# gps.net
KiCad netlist of a schematic drawn in EAGLE
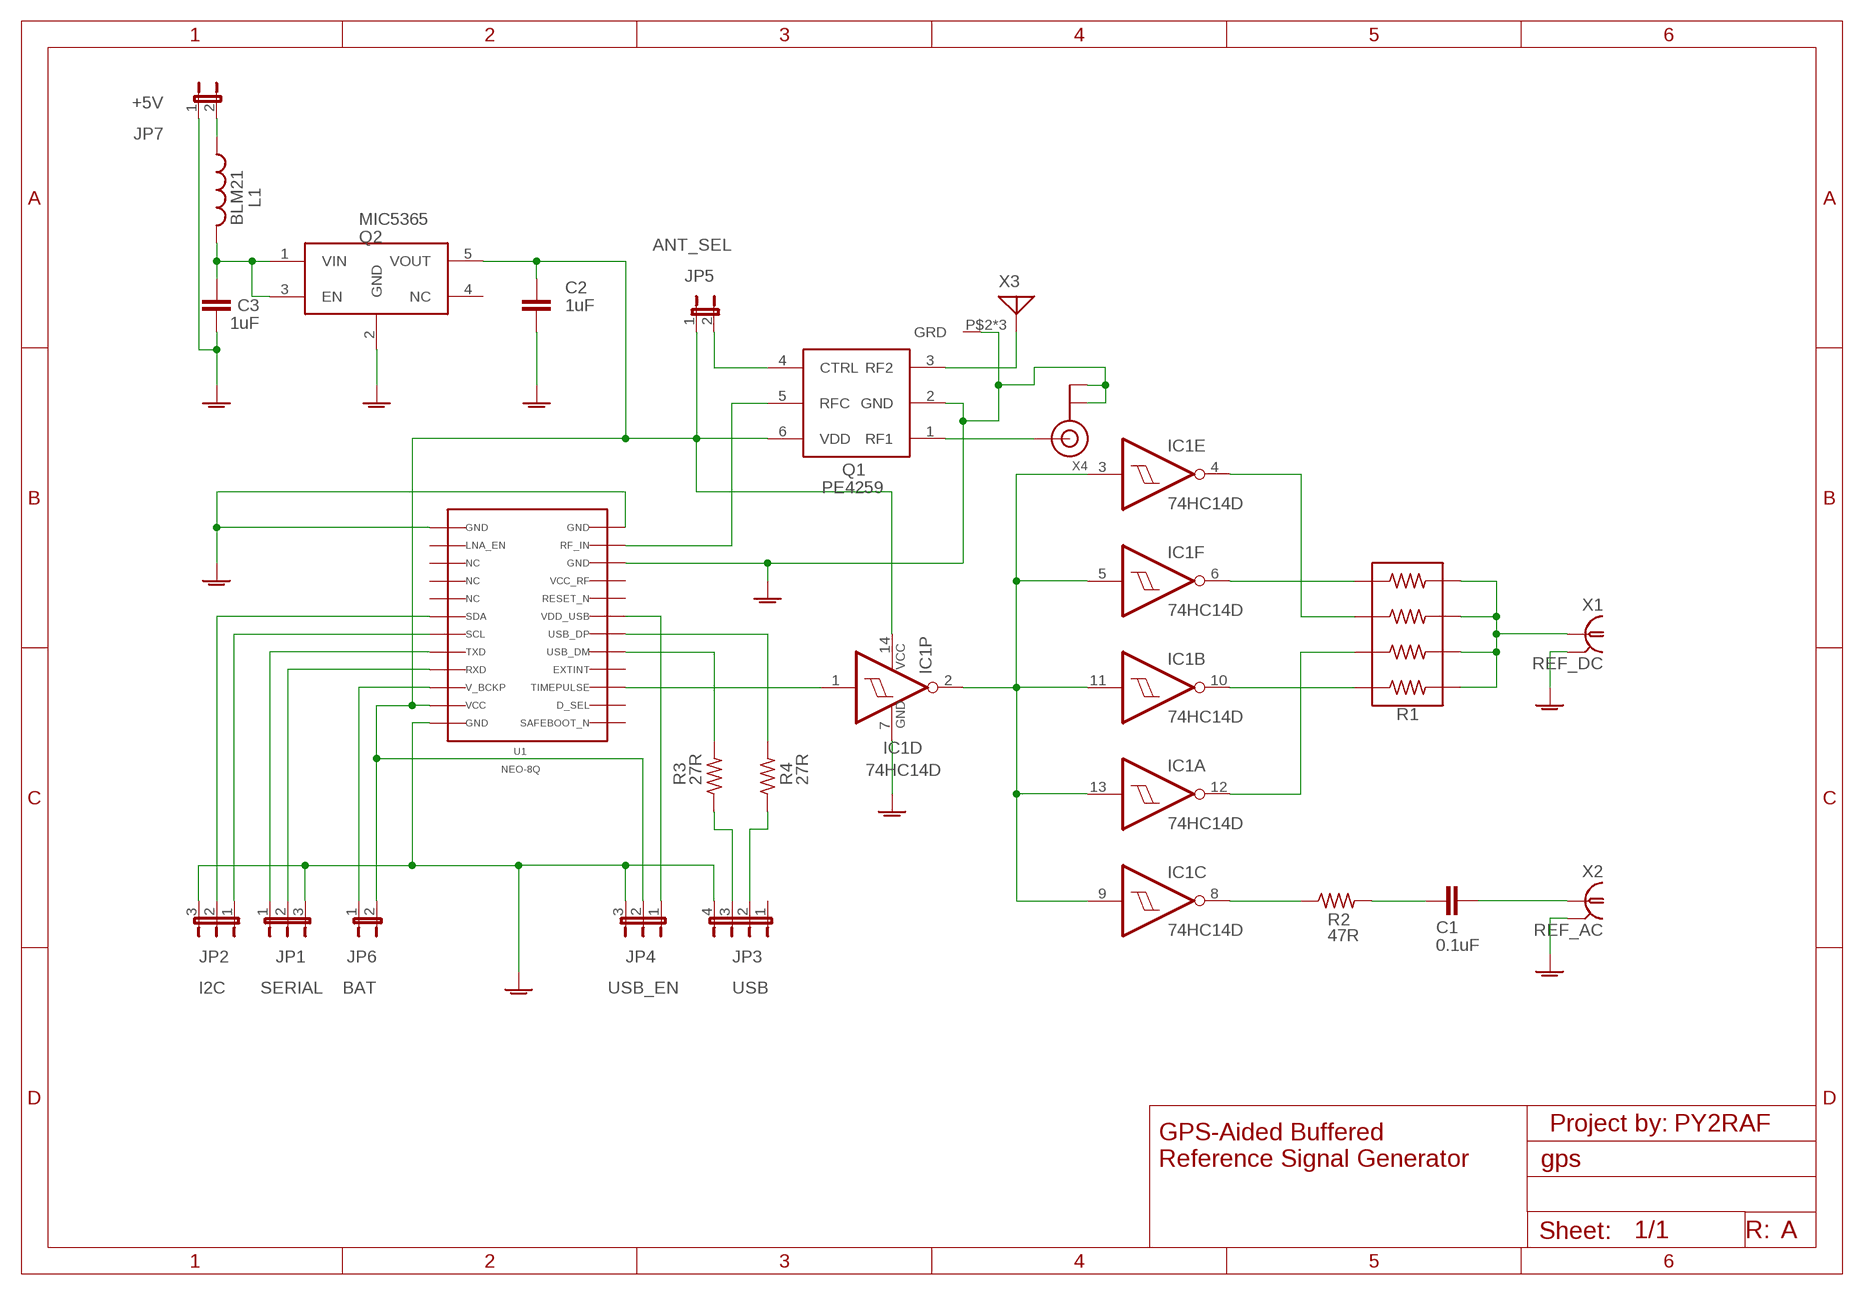
[diagram p0: schematic, sheet 1]

(export (version "E")
  (design (tool "Eeschema 10.0.6"))
  (components
    (comp (ref "C1")
      (value "0.1uF")
      (footprint "eagle-import:C1206")
      (libsource (lib "eagle-import") (part "C-EUC1206"))
    )
    (comp (ref "C2")
      (value "1uF")
      (footprint "eagle-import:C1206")
      (libsource (lib "eagle-import") (part "C-EUC1206"))
    )
    (comp (ref "C3")
      (value "1uF")
      (footprint "eagle-import:C1206")
      (libsource (lib "eagle-import") (part "C-EUC1206"))
    )
    (comp (ref "IC1")
      (value "74HC14D")
      (footprint "eagle-import:SO14")
      (libsource (lib "eagle-import") (part "7414DHC"))
    )
    (comp (ref "JP1")
      (value "SERIAL")
      (footprint "eagle-import:JP2")
      (libsource (lib "eagle-import") (part "JP2E"))
    )
    (comp (ref "JP2")
      (value "I2C")
      (footprint "eagle-import:JP2")
      (libsource (lib "eagle-import") (part "JP2E"))
    )
    (comp (ref "JP3")
      (value "USB")
      (footprint "eagle-import:JP4")
      (libsource (lib "eagle-import") (part "JP4E"))
    )
    (comp (ref "JP4")
      (value "USB_EN")
      (footprint "eagle-import:JP2")
      (libsource (lib "eagle-import") (part "JP2E"))
    )
    (comp (ref "JP5")
      (value "ANT_SEL")
      (footprint "eagle-import:JP1")
      (libsource (lib "eagle-import") (part "JP1E"))
    )
    (comp (ref "JP6")
      (value "BAT")
      (footprint "eagle-import:JP1")
      (libsource (lib "eagle-import") (part "JP1E"))
    )
    (comp (ref "JP7")
      (value "+5V")
      (footprint "eagle-import:JP1")
      (libsource (lib "eagle-import") (part "JP1E"))
    )
    (comp (ref "L1")
      (value "BLM21")
      (footprint "eagle-import:L2012C")
      (libsource (lib "eagle-import") (part "L-USL2012C"))
    )
    (comp (ref "Q1")
      (value "PE4259")
      (footprint "eagle-import:SC-70")
      (libsource (lib "eagle-import") (part "PE4259"))
    )
    (comp (ref "Q2")
      (value "MIC5365")
      (footprint "eagle-import:SOT23-5L")
      (libsource (lib "eagle-import") (part "MIC5365"))
    )
    (comp (ref "R1")
      (value "744C083")
      (footprint "eagle-import:1206X4")
      (libsource (lib "eagle-import") (part "744C083"))
    )
    (comp (ref "R2")
      (value "47R")
      (footprint "eagle-import:M1206")
      (libsource (lib "eagle-import") (part "R-US_M1206"))
    )
    (comp (ref "R3")
      (value "27R")
      (footprint "eagle-import:M1206")
      (libsource (lib "eagle-import") (part "R-US_M1206"))
    )
    (comp (ref "R4")
      (value "27R")
      (footprint "eagle-import:M1206")
      (libsource (lib "eagle-import") (part "R-US_M1206"))
    )
    (comp (ref "U1")
      (value "NEO-8Q")
      (footprint "eagle-import:NEO-7")
      (libsource (lib "eagle-import") (part "NEO-8"))
    )
    (comp (ref "X1")
      (value "REF_DC")
      (footprint "eagle-import:SMA-RF")
      (libsource (lib "eagle-import") (part "SMA-PCB"))
    )
    (comp (ref "X2")
      (value "REF_AC")
      (footprint "eagle-import:SMA-RF")
      (libsource (lib "eagle-import") (part "SMA-PCB"))
    )
    (comp (ref "X3")
      (value "ANT-GNSS-MLX")
      (footprint "eagle-import:MOLEX-GNSS")
      (libsource (lib "eagle-import") (part "ANT-GNSS-MLX"))
    )
    (comp (ref "X4")
      (value "ANTENNA_U.FL")
      (footprint "eagle-import:U.FL")
      (libsource (lib "eagle-import") (part "ANTENNA_U.FL"))
    )
  )
  (nets
    (net (code "1") (name "GNDA") (class "Default")
      (node (ref "C2") (pin "2") (pinfunction "2_2") (pintype "passive"))
      (node (ref "C3") (pin "2") (pinfunction "2_2") (pintype "passive"))
      (node (ref "IC1") (pin "7") (pinfunction "GND_7") (pintype "power_in"))
      (node (ref "JP1") (pin "3") (pinfunction "3_3") (pintype "passive"))
      (node (ref "JP2") (pin "3") (pinfunction "3_3") (pintype "passive"))
      (node (ref "JP3") (pin "4") (pinfunction "4_4") (pintype "passive"))
      (node (ref "JP4") (pin "3") (pinfunction "3_3") (pintype "passive"))
      (node (ref "JP7") (pin "1") (pinfunction "1_1") (pintype "passive"))
      (node (ref "Q1") (pin "2") (pinfunction "GND_2") (pintype "bidirectional"))
      (node (ref "Q2") (pin "2") (pinfunction "GND_2") (pintype "bidirectional"))
      (node (ref "U1") (pin "10") (pinfunction "P$10_10") (pintype "bidirectional"))
      (node (ref "U1") (pin "12") (pinfunction "P$12_12") (pintype "bidirectional"))
      (node (ref "U1") (pin "13") (pinfunction "P$13_13") (pintype "bidirectional"))
      (node (ref "U1") (pin "24") (pinfunction "P$24_24") (pintype "bidirectional"))
      (node (ref "X1") (pin "2") (pinfunction "2_2") (pintype "passive"))
      (node (ref "X1") (pin "3") (pinfunction "2_3") (pintype "passive"))
      (node (ref "X1") (pin "4") (pinfunction "2_4") (pintype "passive"))
      (node (ref "X1") (pin "5") (pinfunction "2_5") (pintype "passive"))
      (node (ref "X2") (pin "2") (pinfunction "2_2") (pintype "passive"))
      (node (ref "X2") (pin "3") (pinfunction "2_3") (pintype "passive"))
      (node (ref "X2") (pin "4") (pinfunction "2_4") (pintype "passive"))
      (node (ref "X2") (pin "5") (pinfunction "2_5") (pintype "passive"))
      (node (ref "X3") (pin "P$2") (pinfunction "GRD_P$2") (pintype "bidirectional"))
      (node (ref "X3") (pin "P$3") (pinfunction "GRD_P$3") (pintype "bidirectional"))
      (node (ref "X3") (pin "P$4") (pinfunction "GRD_P$4") (pintype "bidirectional"))
      (node (ref "X4") (pin "1") (pinfunction "GND_1") (pintype "passive"))
      (node (ref "X4") (pin "2") (pinfunction "GND_2") (pintype "passive"))
    )
    (net (code "2") (name "Net-(C1-Pad1)") (class "Default")
      (node (ref "C1") (pin "1") (pinfunction "1_1") (pintype "passive"))
      (node (ref "X2") (pin "1") (pinfunction "1_1") (pintype "passive"))
    )
    (net (code "3") (name "Net-(C1-Pad2)") (class "Default")
      (node (ref "C1") (pin "2") (pinfunction "2_2") (pintype "passive"))
      (node (ref "R2") (pin "2") (pinfunction "2_2") (pintype "passive"))
    )
    (net (code "4") (name "Net-(IC1A-I)") (class "Default")
      (node (ref "IC1") (pin "11") (pinfunction "I_11") (pintype "input"))
      (node (ref "IC1") (pin "13") (pinfunction "I_13") (pintype "input"))
      (node (ref "IC1") (pin "2") (pinfunction "O_2") (pintype "output"))
      (node (ref "IC1") (pin "3") (pinfunction "I_3") (pintype "input"))
      (node (ref "IC1") (pin "5") (pinfunction "I_5") (pintype "input"))
      (node (ref "IC1") (pin "9") (pinfunction "I_9") (pintype "input"))
    )
    (net (code "5") (name "Net-(IC1A-O)") (class "Default")
      (node (ref "IC1") (pin "12") (pinfunction "O_12") (pintype "output"))
      (node (ref "R1") (pin "P$2") (pinfunction "2_P$2") (pintype "passive"))
    )
    (net (code "6") (name "Net-(IC1B-O)") (class "Default")
      (node (ref "IC1") (pin "10") (pinfunction "O_10") (pintype "output"))
      (node (ref "R1") (pin "P$1") (pinfunction "1_P$1") (pintype "passive"))
    )
    (net (code "7") (name "Net-(IC1C-O)") (class "Default")
      (node (ref "IC1") (pin "8") (pinfunction "O_8") (pintype "output"))
      (node (ref "R2") (pin "1") (pinfunction "1_1") (pintype "passive"))
    )
    (net (code "8") (name "Net-(IC1D-I)") (class "Default")
      (node (ref "IC1") (pin "1") (pinfunction "I_1") (pintype "input"))
      (node (ref "U1") (pin "3") (pinfunction "P$3_3") (pintype "bidirectional"))
    )
    (net (code "9") (name "Net-(IC1E-O)") (class "Default")
      (node (ref "IC1") (pin "4") (pinfunction "O_4") (pintype "output"))
      (node (ref "R1") (pin "P$3") (pinfunction "3_P$3") (pintype "passive"))
    )
    (net (code "10") (name "Net-(IC1F-O)") (class "Default")
      (node (ref "IC1") (pin "6") (pinfunction "O_6") (pintype "output"))
      (node (ref "R1") (pin "P$4") (pinfunction "4_P$4") (pintype "passive"))
    )
    (net (code "11") (name "Net-(IC1G-VCC)") (class "Default")
      (node (ref "C2") (pin "1") (pinfunction "1_1") (pintype "passive"))
      (node (ref "IC1") (pin "14") (pinfunction "VCC_14") (pintype "power_in"))
      (node (ref "JP4") (pin "2") (pinfunction "2_2") (pintype "passive"))
      (node (ref "JP5") (pin "1") (pinfunction "1_1") (pintype "passive"))
      (node (ref "JP6") (pin "2") (pinfunction "2_2") (pintype "passive"))
      (node (ref "Q1") (pin "6") (pinfunction "VDD_6") (pintype "power_in"))
      (node (ref "Q2") (pin "5") (pinfunction "VOUT_5") (pintype "bidirectional"))
      (node (ref "U1") (pin "23") (pinfunction "P$23_23") (pintype "bidirectional"))
    )
    (net (code "12") (name "Net-(JP3-Pad2)") (class "Default")
      (node (ref "JP3") (pin "2") (pinfunction "2_2") (pintype "passive"))
      (node (ref "R4") (pin "1") (pinfunction "1_1") (pintype "passive"))
    )
    (net (code "13") (name "Net-(JP3-Pad3)") (class "Default")
      (node (ref "JP3") (pin "3") (pinfunction "3_3") (pintype "passive"))
      (node (ref "R3") (pin "1") (pinfunction "1_1") (pintype "passive"))
    )
    (net (code "14") (name "Net-(JP7-Pad2)") (class "Default")
      (node (ref "JP7") (pin "2") (pinfunction "2_2") (pintype "passive"))
      (node (ref "L1") (pin "1") (pinfunction "1_1") (pintype "passive"))
    )
    (net (code "15") (name "Net-(Q1-CTRL)") (class "Default")
      (node (ref "JP5") (pin "2") (pinfunction "2_2") (pintype "passive"))
      (node (ref "Q1") (pin "4") (pinfunction "CTRL_4") (pintype "input"))
    )
    (net (code "16") (name "Net-(Q1-RF1)") (class "Default")
      (node (ref "Q1") (pin "1") (pinfunction "RF1_1") (pintype "bidirectional"))
      (node (ref "X4") (pin "3") (pinfunction "SIGNAL_3") (pintype "passive"))
    )
    (net (code "17") (name "Net-(Q1-RF2)") (class "Default")
      (node (ref "Q1") (pin "3") (pinfunction "RF2_3") (pintype "bidirectional"))
      (node (ref "X3") (pin "P$1") (pinfunction "ANT_P$1") (pintype "output"))
    )
    (net (code "18") (name "Net-(Q1-RFC)") (class "Default")
      (node (ref "Q1") (pin "5") (pinfunction "RFC_5") (pintype "bidirectional"))
      (node (ref "U1") (pin "11") (pinfunction "P$11_11") (pintype "bidirectional"))
    )
    (net (code "19") (name "Net-(Q2-EN)") (class "Default")
      (node (ref "C3") (pin "1") (pinfunction "1_1") (pintype "passive"))
      (node (ref "L1") (pin "2") (pinfunction "2_2") (pintype "passive"))
      (node (ref "Q2") (pin "1") (pinfunction "VIN_1") (pintype "bidirectional"))
      (node (ref "Q2") (pin "3") (pinfunction "EN_3") (pintype "bidirectional"))
    )
    (net (code "20") (name "Net-(R1-5)") (class "Default")
      (node (ref "R1") (pin "P$5") (pinfunction "5_P$5") (pintype "passive"))
      (node (ref "R1") (pin "P$6") (pinfunction "6_P$6") (pintype "passive"))
      (node (ref "R1") (pin "P$7") (pinfunction "7_P$7") (pintype "passive"))
      (node (ref "R1") (pin "P$8") (pinfunction "8_P$8") (pintype "passive"))
      (node (ref "X1") (pin "1") (pinfunction "1_1") (pintype "passive"))
    )
    (net (code "21") (name "Net-(U1-P$5)") (class "Default")
      (node (ref "R3") (pin "2") (pinfunction "2_2") (pintype "passive"))
      (node (ref "U1") (pin "5") (pinfunction "P$5_5") (pintype "bidirectional"))
    )
    (net (code "22") (name "Net-(U1-P$6)") (class "Default")
      (node (ref "R4") (pin "2") (pinfunction "2_2") (pintype "passive"))
      (node (ref "U1") (pin "6") (pinfunction "P$6_6") (pintype "bidirectional"))
    )
    (net (code "23") (name "Net-(U1-P$7)") (class "Default")
      (node (ref "JP4") (pin "1") (pinfunction "1_1") (pintype "passive"))
      (node (ref "U1") (pin "7") (pinfunction "P$7_7") (pintype "bidirectional"))
    )
    (net (code "24") (name "Net-(U1-P$18)") (class "Default")
      (node (ref "JP2") (pin "2") (pinfunction "2_2") (pintype "passive"))
      (node (ref "U1") (pin "18") (pinfunction "P$18_18") (pintype "bidirectional"))
    )
    (net (code "25") (name "Net-(U1-P$19)") (class "Default")
      (node (ref "JP2") (pin "1") (pinfunction "1_1") (pintype "passive"))
      (node (ref "U1") (pin "19") (pinfunction "P$19_19") (pintype "bidirectional"))
    )
    (net (code "26") (name "Net-(U1-P$20)") (class "Default")
      (node (ref "JP1") (pin "1") (pinfunction "1_1") (pintype "passive"))
      (node (ref "U1") (pin "20") (pinfunction "P$20_20") (pintype "bidirectional"))
    )
    (net (code "27") (name "Net-(U1-P$21)") (class "Default")
      (node (ref "JP1") (pin "2") (pinfunction "2_2") (pintype "passive"))
      (node (ref "U1") (pin "21") (pinfunction "P$21_21") (pintype "bidirectional"))
    )
    (net (code "28") (name "Net-(U1-P$22)") (class "Default")
      (node (ref "JP6") (pin "1") (pinfunction "1_1") (pintype "passive"))
      (node (ref "U1") (pin "22") (pinfunction "P$22_22") (pintype "bidirectional"))
    )
    (net (code "29") (name "unconnected-(JP3-Pad1)") (class "Default")
      (node (ref "JP3") (pin "1") (pinfunction "1_1") (pintype "passive"))
    )
    (net (code "30") (name "unconnected-(Q2-NC-Pad4)") (class "Default")
      (node (ref "Q2") (pin "4") (pinfunction "NC_4") (pintype "bidirectional"))
    )
    (net (code "31") (name "unconnected-(U1-P$1-Pad1)") (class "Default")
      (node (ref "U1") (pin "1") (pinfunction "P$1_1") (pintype "bidirectional"))
    )
    (net (code "32") (name "unconnected-(U1-P$2-Pad2)") (class "Default")
      (node (ref "U1") (pin "2") (pinfunction "P$2_2") (pintype "bidirectional"))
    )
    (net (code "33") (name "unconnected-(U1-P$4-Pad4)") (class "Default")
      (node (ref "U1") (pin "4") (pinfunction "P$4_4") (pintype "bidirectional"))
    )
    (net (code "34") (name "unconnected-(U1-P$8-Pad8)") (class "Default")
      (node (ref "U1") (pin "8") (pinfunction "P$8_8") (pintype "bidirectional"))
    )
    (net (code "35") (name "unconnected-(U1-P$9-Pad9)") (class "Default")
      (node (ref "U1") (pin "9") (pinfunction "P$9_9") (pintype "bidirectional"))
    )
    (net (code "36") (name "unconnected-(U1-P$14-Pad14)") (class "Default")
      (node (ref "U1") (pin "14") (pinfunction "P$14_14") (pintype "bidirectional"))
    )
    (net (code "37") (name "unconnected-(U1-P$15-Pad15)") (class "Default")
      (node (ref "U1") (pin "15") (pinfunction "P$15_15") (pintype "bidirectional"))
    )
    (net (code "38") (name "unconnected-(U1-P$16-Pad16)") (class "Default")
      (node (ref "U1") (pin "16") (pinfunction "P$16_16") (pintype "bidirectional"))
    )
    (net (code "39") (name "unconnected-(U1-P$17-Pad17)") (class "Default")
      (node (ref "U1") (pin "17") (pinfunction "P$17_17") (pintype "bidirectional"))
    )
  )
)
